# schematic.net
KiCad netlist of a schematic drawn in EasyEDA
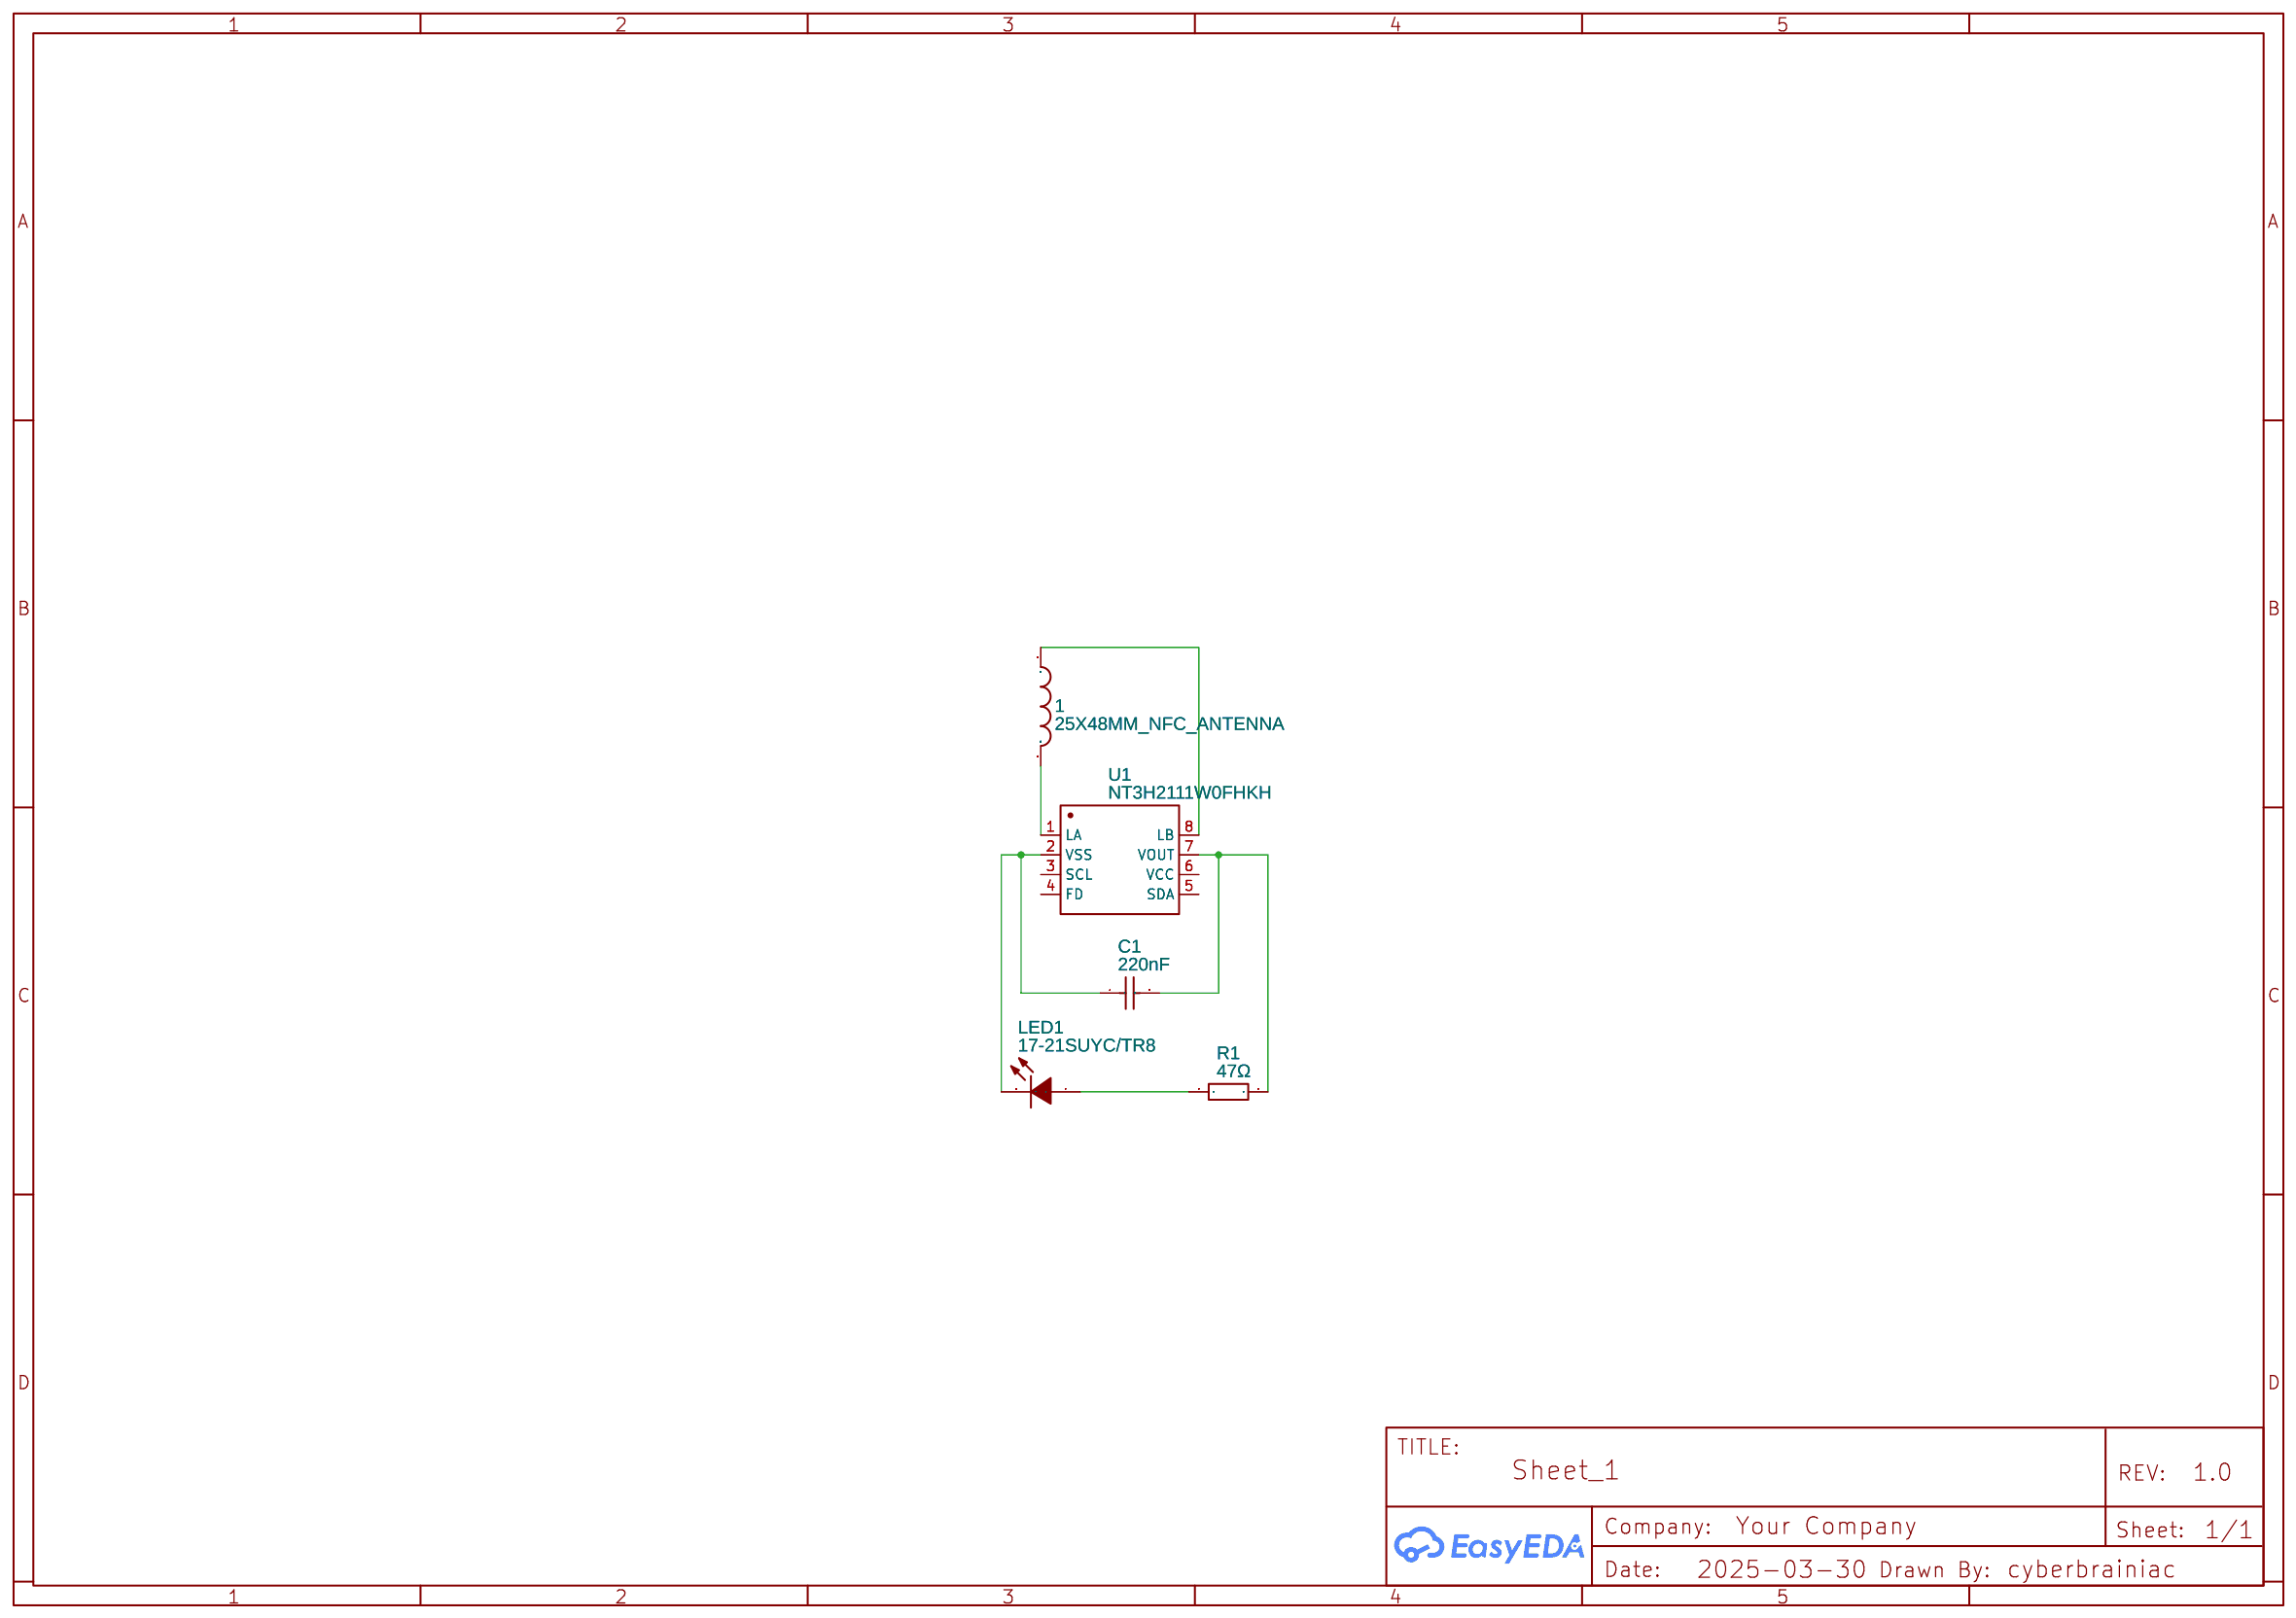
[diagram p0: schematic sheet]

(export (version "E")
  (design (tool "Eeschema 10.0.6"))
  (components
    (comp (ref "1") (value "25X48MM_NFC_ANTENNA") (libsource (lib "") (part "25X48MM_NFC_ANTENNA")))
    (comp (ref "C1")
      (value "220nF")
      (fields
        (field (name "Manufacturer Part") "CL10B224KB8NNNC")
        (field (name "Manufacturer") "SAMSUNG(三星)")
      )
      (libsource (lib "") (part "CL10B224KB8NNNC"))
    )
    (comp (ref "LED1")
      (value "17-21SUYC/TR8")
      (fields (field (name "Manufacturer Part") "KT-0805黄灯") (field (name "Manufacturer") "KENTO"))
      (libsource (lib "") (part "17-21SUYC/TR8"))
    )
    (comp (ref "R1")
      (value "47Ω")
      (fields
        (field (name "Manufacturer Part") "0603WAF470JT5E")
        (field (name "Manufacturer") "UNI-ROYAL(厚声)")
      )
      (libsource (lib "") (part "0603WAF470JT5E"))
    )
    (comp (ref "U1")
      (value "NT3H2111W0FHKH")
      (fields (field (name "Manufacturer") "NXP(恩智浦)"))
      (libsource (lib "") (part "NT3H2111W0FHKH"))
    )
  )
  (nets
    (net (code "1") (name "Net-(LED1-+)") (class "Default")
      (node (ref "LED1") (pin "1") (pinfunction "+_1") (pintype "unspecified"))
      (node (ref "R1") (pin "1") (pinfunction "1_1") (pintype "input"))
    )
    (net (code "2") (name "Net-(LED1--)") (class "Default")
      (node (ref "C1") (pin "1") (pinfunction "1_1") (pintype "input"))
      (node (ref "LED1") (pin "2") (pinfunction "-_2") (pintype "unspecified"))
      (node (ref "U1") (pin "2") (pinfunction "VSS_2") (pintype "unspecified"))
    )
    (net (code "3") (name "Net-(U1-LA)") (class "Default")
      (node (ref "1") (pin "P$2") (pinfunction "P$2_P$2") (pintype "bidirectional"))
      (node (ref "U1") (pin "1") (pinfunction "LA_1") (pintype "unspecified"))
    )
    (net (code "4") (name "Net-(U1-LB)") (class "Default")
      (node (ref "1") (pin "P$1") (pinfunction "P$1_P$1") (pintype "bidirectional"))
      (node (ref "U1") (pin "8") (pinfunction "LB_8") (pintype "unspecified"))
    )
    (net (code "5") (name "Net-(U1-VOUT)") (class "Default")
      (node (ref "C1") (pin "2") (pinfunction "2_2") (pintype "input"))
      (node (ref "R1") (pin "2") (pinfunction "2_2") (pintype "input"))
      (node (ref "U1") (pin "7") (pinfunction "VOUT_7") (pintype "unspecified"))
    )
    (net (code "6") (name "unconnected-(U1-FD-Pad4)") (class "Default")
      (node (ref "U1") (pin "4") (pinfunction "FD_4") (pintype "unspecified"))
    )
    (net (code "7") (name "unconnected-(U1-SCL-Pad3)") (class "Default")
      (node (ref "U1") (pin "3") (pinfunction "SCL_3") (pintype "unspecified"))
    )
    (net (code "8") (name "unconnected-(U1-SDA-Pad5)") (class "Default")
      (node (ref "U1") (pin "5") (pinfunction "SDA_5") (pintype "unspecified"))
    )
    (net (code "9") (name "unconnected-(U1-VCC-Pad6)") (class "Default")
      (node (ref "U1") (pin "6") (pinfunction "VCC_6") (pintype "unspecified"))
    )
  )
)
